# B-4-carte.net
KiCad netlist of a schematic drawn in EAGLE
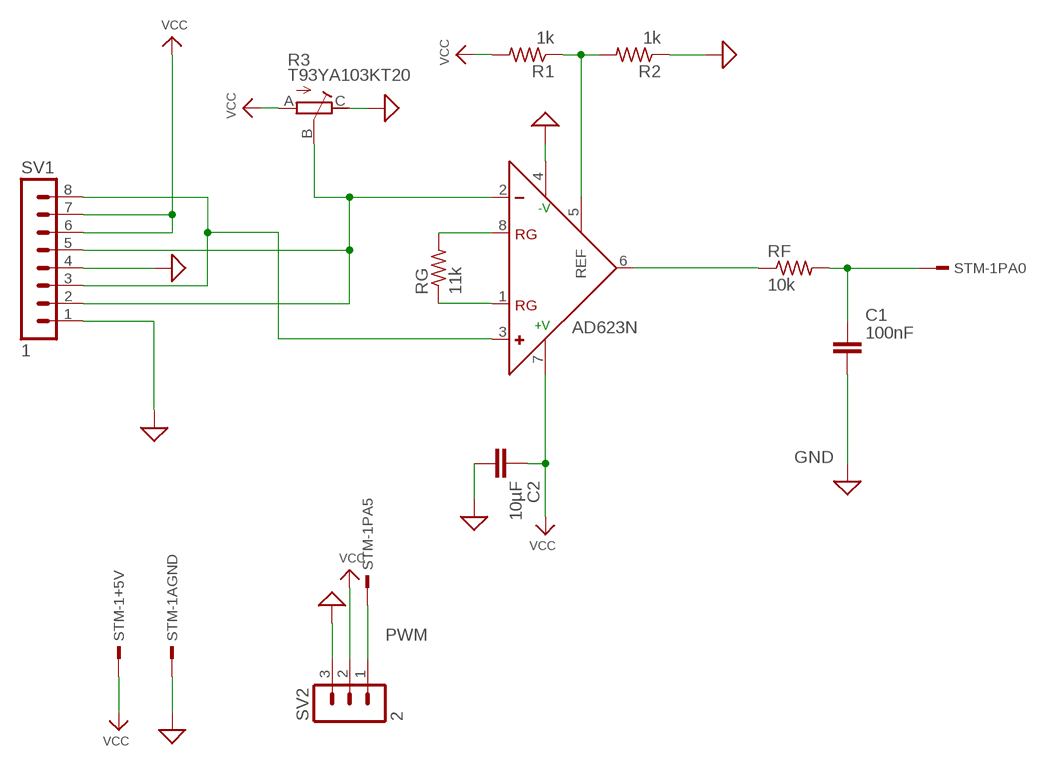
[diagram p0: schematic, sheet 1]

(export (version "E")
  (design (tool "Eeschema 10.0.6"))
  (components
    (comp (ref "C1")
      (value "100nF")
      (footprint "eagle-import:C2.5-2")
      (libsource (lib "eagle-import") (part "C2.5/2"))
    )
    (comp (ref "C2")
      (value "10µF")
      (footprint "eagle-import:C2.5-2")
      (libsource (lib "eagle-import") (part "C2.5/2"))
    )
    (comp (ref "IC1")
      (value "AD623N")
      (footprint "eagle-import:DIL08")
      (fields (field (name "MF") "ALTERA CORPORATION") (field (name "MPN") "AD623ANZ"))
      (libsource (lib "eagle-import") (part "AD623N"))
    )
    (comp (ref "R1")
      (value "1k")
      (footprint "eagle-import:0204_7")
      (libsource (lib "eagle-import") (part "adafruit_420_R-US_0204/7"))
    )
    (comp (ref "R2")
      (value "1k")
      (footprint "eagle-import:0204_7")
      (libsource (lib "eagle-import") (part "R-US_0204/7"))
    )
    (comp (ref "R3")
      (value "T93YA103KT20")
      (footprint "eagle-import:TRIM_T93YA103KT20")
      (fields (field (name "MF") "Vishay"))
      (libsource (lib "eagle-import") (part "T93YA103KT20"))
    )
    (comp (ref "RF")
      (value "10k")
      (footprint "eagle-import:0204_7")
      (libsource (lib "eagle-import") (part "R-US_0204/7"))
    )
    (comp (ref "RG")
      (value "11k")
      (footprint "eagle-import:0204_7")
      (libsource (lib "eagle-import") (part "adafruit_420_R-US_0204/7"))
    )
    (comp (ref "STM-1")
      (value "NUCLEO-F411RE")
      (footprint "eagle-import:CONN_STM32_NUCLEO")
      (libsource (lib "eagle-import") (part "NUCLEO-F411RE"))
    )
    (comp (ref "SV1")
      (value "1")
      (footprint "eagle-import:MA08-1")
      (libsource (lib "eagle-import") (part "MA08-1"))
    )
    (comp (ref "SV2")
      (value "2")
      (footprint "eagle-import:MA03-1")
      (libsource (lib "eagle-import") (part "MA03-1"))
    )
  )
  (nets
    (net (code "1") (name "/PWM") (class "Default")
      (node (ref "STM-1") (pin "49") (pinfunction "1_49") (pintype "passive"))
      (node (ref "SV2") (pin "1") (pinfunction "1_1") (pintype "passive"))
    )
    (net (code "2") (name "Net-(IC1-+)") (class "Default")
      (node (ref "IC1") (pin "3") (pinfunction "+_3") (pintype "input"))
      (node (ref "SV1") (pin "3") (pinfunction "3_3") (pintype "passive"))
      (node (ref "SV1") (pin "8") (pinfunction "8_8") (pintype "passive"))
    )
    (net (code "3") (name "Net-(IC1--)") (class "Default")
      (node (ref "IC1") (pin "2") (pinfunction "-_2") (pintype "input"))
      (node (ref "R3") (pin "B") (pinfunction "B_B") (pintype "passive"))
      (node (ref "SV1") (pin "2") (pinfunction "2_2") (pintype "passive"))
      (node (ref "SV1") (pin "5") (pinfunction "5_5") (pintype "passive"))
    )
    (net (code "4") (name "Net-(IC1-OUT)") (class "Default")
      (node (ref "IC1") (pin "6") (pinfunction "OUT_6") (pintype "output"))
      (node (ref "RF") (pin "1") (pinfunction "1_1") (pintype "passive"))
    )
    (net (code "5") (name "Net-(IC1-REF)") (class "Default")
      (node (ref "IC1") (pin "5") (pinfunction "REF_5") (pintype "passive"))
      (node (ref "R1") (pin "1") (pinfunction "1_1") (pintype "passive"))
      (node (ref "R2") (pin "2") (pinfunction "2_2") (pintype "passive"))
    )
    (net (code "6") (name "Net-(IC1-RG-Pad1)") (class "Default")
      (node (ref "IC1") (pin "1") (pinfunction "RG_1") (pintype "passive"))
      (node (ref "RG") (pin "1") (pinfunction "1_1") (pintype "passive"))
    )
    (net (code "7") (name "Net-(IC1-RG-Pad8)") (class "Default")
      (node (ref "IC1") (pin "8") (pinfunction "RG_8") (pintype "passive"))
      (node (ref "RG") (pin "2") (pinfunction "2_2") (pintype "passive"))
    )
    (net (code "8") (name "Net-(STM-1V-1)") (class "Default")
      (node (ref "C1") (pin "1") (pinfunction "1_1") (pintype "passive"))
      (node (ref "RF") (pin "2") (pinfunction "2_2") (pintype "passive"))
      (node (ref "STM-1") (pin "28") (pinfunction "1_28") (pintype "passive"))
    )
    (net (code "9") (name "SUP") (class "Default")
      (node (ref "C1") (pin "2") (pinfunction "2_2") (pintype "passive"))
      (node (ref "C2") (pin "2") (pinfunction "2_2") (pintype "passive"))
      (node (ref "IC1") (pin "4") (pinfunction "-V_4") (pintype "power_in"))
      (node (ref "R2") (pin "1") (pinfunction "1_1") (pintype "passive"))
      (node (ref "R3") (pin "C") (pinfunction "C_C") (pintype "passive"))
      (node (ref "STM-1") (pin "70") (pinfunction "1_70") (pintype "passive"))
      (node (ref "SV1") (pin "1") (pinfunction "1_1") (pintype "passive"))
      (node (ref "SV1") (pin "4") (pinfunction "4_4") (pintype "passive"))
      (node (ref "SV2") (pin "3") (pinfunction "3_3") (pintype "passive"))
    )
    (net (code "10") (name "VCC") (class "Default")
      (node (ref "C2") (pin "1") (pinfunction "1_1") (pintype "passive"))
      (node (ref "IC1") (pin "7") (pinfunction "+V_7") (pintype "power_in"))
      (node (ref "R1") (pin "2") (pinfunction "2_2") (pintype "passive"))
      (node (ref "R3") (pin "A") (pinfunction "A_A") (pintype "passive"))
      (node (ref "STM-1") (pin "18") (pinfunction "1_18") (pintype "passive"))
      (node (ref "SV1") (pin "6") (pinfunction "6_6") (pintype "passive"))
      (node (ref "SV1") (pin "7") (pinfunction "7_7") (pintype "passive"))
      (node (ref "SV2") (pin "2") (pinfunction "2_2") (pintype "passive"))
    )
  )
)
